# ISO_I2C_ISO1540DR.net
KiCad netlist of a schematic drawn in Altium Designer
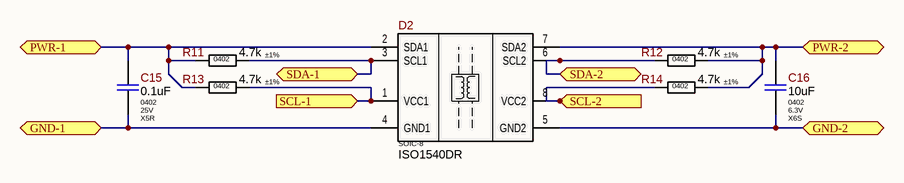
[diagram p0: ISO_I2C_ISO1540DR.SchDoc]

(export (version "E")
  (design (tool "Eeschema 10.0.6"))
  (components
    (comp (ref "C15")
      (value "0.1uF")
      (footprint "C_CERAMIC_0402_MED")
      (description "100nF 25V X5R ±10% 0402 Ceramic Capacitor RoHS")
      (fields
        (field (name "PACKAGE") "0402")
        (field (name "VOLTAGE") "25V")
        (field (name "DIELECTRIC TYPE") "X5R")
        (field (name "PART NUMBER") "CL05A104KA5NNNC")
        (field (name "MANUFACTURER") "Samsung Electro-Mechanics")
      )
      (libsource (lib "EL.XXX.T01") (part "Capacitor-NonPolar"))
    )
    (comp (ref "C16")
      (value "10uF")
      (footprint "C_CERAMIC_0402_MED")
      (description "10uF 6.3V X6S ±20% 0402 Ceramic Capacitor RoHS")
      (fields
        (field (name "PACKAGE") "0402")
        (field (name "VOLTAGE") "6.3V")
        (field (name "DIELECTRIC TYPE") "X6S")
        (field (name "PART NUMBER") "GRM155C80J106ME11D")
        (field (name "MANUFACTURER") "Murata Electronics")
      )
      (libsource (lib "EL.XXX.T01") (part "Capacitor-NonPolar"))
    )
    (comp (ref "D2")
      (value "ISO1540DR")
      (footprint "SOIC-8_W3.9MM")
      (description "I2C Digital Isolator 2500Vrms 2 Channel 1Mbps 25kV/us, SOIC-8")
      (fields
        (field (name "PACKAGE") "SOIC-8")
        (field (name "PART NUMBER") "ISO1540DR")
        (field (name "MANUFACTURER") "Texas Instruments")
      )
      (libsource (lib "EL.XXX.T01") (part "ISO1540DR"))
    )
    (comp (ref "R11")
      (value "4.7k")
      (footprint "R_ANY_CHIP_0402_MED")
      (description "4.7 kOhms ±1% 1/16W 0402 Thick Film Resistor")
      (fields
        (field (name "TOLERANCE") "±1%")
        (field (name "PACKAGE") "0402")
        (field (name "PART NUMBER") "RC0402FR-074K7L")
        (field (name "MANUFACTURER") "Yageo")
      )
      (libsource (lib "EL.XXX.T01") (part "Resistor"))
    )
    (comp (ref "R12")
      (value "4.7k")
      (footprint "R_ANY_CHIP_0402_MED")
      (description "4.7 kOhms ±1% 1/16W 0402 Thick Film Resistor")
      (fields
        (field (name "TOLERANCE") "±1%")
        (field (name "PACKAGE") "0402")
        (field (name "PART NUMBER") "RC0402FR-074K7L")
        (field (name "MANUFACTURER") "Yageo")
      )
      (libsource (lib "EL.XXX.T01") (part "Resistor"))
    )
    (comp (ref "R13")
      (value "4.7k")
      (footprint "R_ANY_CHIP_0402_MED")
      (description "4.7 kOhms ±1% 1/16W 0402 Thick Film Resistor")
      (fields
        (field (name "TOLERANCE") "±1%")
        (field (name "PACKAGE") "0402")
        (field (name "PART NUMBER") "RC0402FR-074K7L")
        (field (name "MANUFACTURER") "Yageo")
      )
      (libsource (lib "EL.XXX.T01") (part "Resistor"))
    )
    (comp (ref "R14")
      (value "4.7k")
      (footprint "R_ANY_CHIP_0402_MED")
      (description "4.7 kOhms ±1% 1/16W 0402 Thick Film Resistor")
      (fields
        (field (name "TOLERANCE") "±1%")
        (field (name "PACKAGE") "0402")
        (field (name "PART NUMBER") "RC0402FR-074K7L")
        (field (name "MANUFACTURER") "Yageo")
      )
      (libsource (lib "EL.XXX.T01") (part "Resistor"))
    )
  )
  (nets
    (net (code "1") (name "/GND-1") (class "Default")
      (node (ref "C15") (pin "2") (pinfunction "2_2") (pintype "passive"))
      (node (ref "D2") (pin "4") (pinfunction "GND1_4") (pintype "passive"))
    )
    (net (code "2") (name "/GND-2") (class "Default")
      (node (ref "C16") (pin "2") (pinfunction "2_2") (pintype "passive"))
      (node (ref "D2") (pin "5") (pinfunction "GND2_5") (pintype "passive"))
    )
    (net (code "3") (name "/PWR-1") (class "Default")
      (node (ref "C15") (pin "1") (pinfunction "1_1") (pintype "passive"))
      (node (ref "D2") (pin "2") (pinfunction "SDA1_2") (pintype "passive"))
      (node (ref "R11") (pin "1") (pintype "passive"))
      (node (ref "R13") (pin "1") (pintype "passive"))
    )
    (net (code "4") (name "/PWR-2") (class "Default")
      (node (ref "C16") (pin "1") (pinfunction "1_1") (pintype "passive"))
      (node (ref "D2") (pin "7") (pinfunction "SDA2_7") (pintype "passive"))
      (node (ref "R12") (pin "2") (pintype "passive"))
      (node (ref "R14") (pin "2") (pintype "passive"))
    )
    (net (code "5") (name "/SCL-1") (class "Default")
      (node (ref "D2") (pin "1") (pinfunction "VCC1_1") (pintype "passive"))
      (node (ref "R13") (pin "2") (pintype "passive"))
    )
    (net (code "6") (name "/SCL-2") (class "Default")
      (node (ref "D2") (pin "8") (pinfunction "VCC2_8") (pintype "passive"))
      (node (ref "R14") (pin "1") (pintype "passive"))
    )
    (net (code "7") (name "/SDA-1") (class "Default")
      (node (ref "D2") (pin "3") (pinfunction "SCL1_3") (pintype "passive"))
      (node (ref "R11") (pin "2") (pintype "passive"))
    )
    (net (code "8") (name "/SDA-2") (class "Default")
      (node (ref "D2") (pin "6") (pinfunction "SCL2_6") (pintype "passive"))
      (node (ref "R12") (pin "1") (pintype "passive"))
    )
  )
)
